# nucleo_breakout.net
KiCad netlist of a schematic drawn in Altium Designer
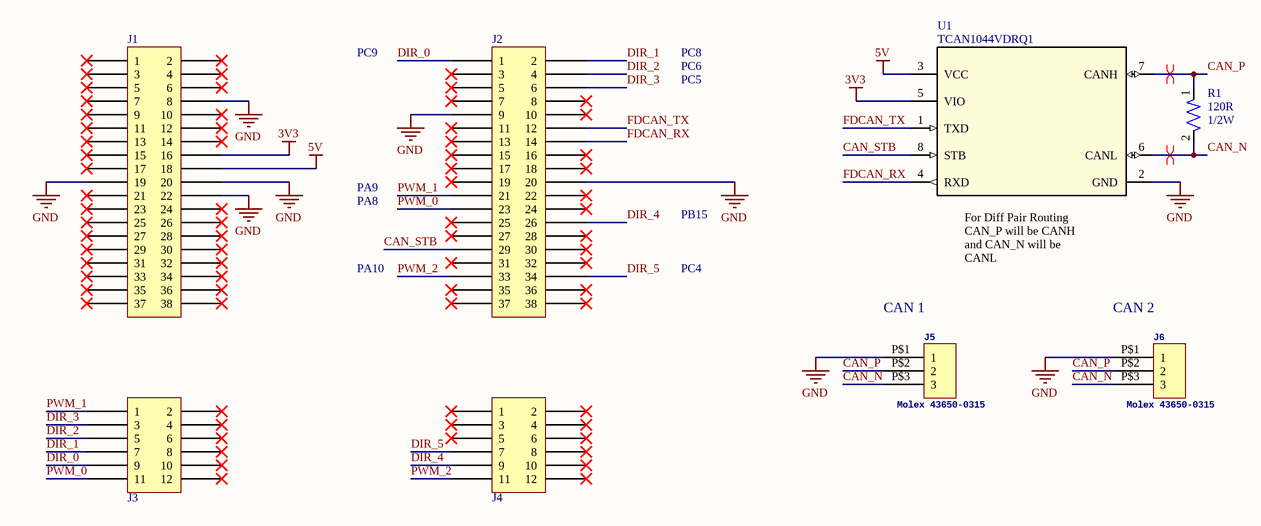
[diagram p0: nucleo_breakout.SchDoc]

(export (version "E")
  (design (tool "Eeschema 10.0.6"))
  (components
    (comp (ref "J1")
      (value "PPPC192LFBN-RC")
      (footprint "CONN-38POS_01")
      (libsource (lib "temp_lib") (part "CONN-38POS-01"))
    )
    (comp (ref "J2")
      (value "PPPC192LFBN-RC")
      (footprint "CONN-38POS_01")
      (libsource (lib "temp_lib") (part "CONN-38POS-01"))
    )
    (comp (ref "J3")
      (value "PPTC062LFBN-RC")
      (footprint "CONN-6POS_01")
      (description "12 Position Header Connector 0.100\" (2.54mm) Through Hole Tin")
      (libsource (lib "temp_lib") (part "CONN-12POS-01"))
    )
    (comp (ref "J4")
      (value "PPTC062LFBN-RC")
      (footprint "CONN-6POS_01")
      (description "12 Position Header Connector 0.100\" (2.54mm) Through Hole Tin")
      (libsource (lib "temp_lib") (part "CONN-12POS-01"))
    )
    (comp (ref "J5")
      (value "Molex 43650-0315")
      (footprint "43650-0315")
      (libsource (lib "Molex Microfit") (part "Micro-Fit Molex 3 Pin Vertical"))
    )
    (comp (ref "J6")
      (value "Molex 43650-0315")
      (footprint "43650-0315")
      (libsource (lib "Molex Microfit") (part "Micro-Fit Molex 3 Pin Vertical"))
    )
    (comp (ref "R1")
      (value "RC1210FR-07120RL")
      (footprint "RES-1210")
      (description "RES 120 OHM 1% 1/2W 1210")
      (fields
        (field (name "TOLERANCE") "1%")
        (field (name "POWER") "1/2W")
        (field (name "RESISTANCE") "120R")
      )
      (libsource (lib "JLC_25") (part "RES-120-0001"))
    )
    (comp (ref "U1")
      (value "TCAN1044VDRQ1")
      (footprint "IC-8SOIC")
      (description "IC TRANSCEIVER 1/1 8SOIC")
      (libsource (lib "JLC_25") (part "IC-CAN-0001"))
    )
  )
  (nets
    (net (code "1") (name "/CAN_N") (class "Default")
      (node (ref "J5") (pin "P$3") (pinfunction "3_P$3") (pintype "passive"))
      (node (ref "J6") (pin "P$3") (pinfunction "3_P$3") (pintype "passive"))
      (node (ref "R1") (pin "2") (pinfunction "2_2") (pintype "passive"))
      (node (ref "U1") (pin "6") (pinfunction "CANL_6") (pintype "bidirectional"))
    )
    (net (code "2") (name "/CAN_P") (class "Default")
      (node (ref "J5") (pin "P$2") (pinfunction "2_P$2") (pintype "passive"))
      (node (ref "J6") (pin "P$2") (pinfunction "2_P$2") (pintype "passive"))
      (node (ref "R1") (pin "1") (pinfunction "1_1") (pintype "passive"))
      (node (ref "U1") (pin "7") (pinfunction "CANH_7") (pintype "bidirectional"))
    )
    (net (code "3") (name "/CAN_STB") (class "Default")
      (node (ref "J2") (pin "29") (pinfunction "29_29") (pintype "passive"))
      (node (ref "U1") (pin "8") (pinfunction "STB_8") (pintype "input"))
    )
    (net (code "4") (name "/DIR_0") (class "Default")
      (node (ref "J2") (pin "1") (pinfunction "1_1") (pintype "passive"))
      (node (ref "J3") (pin "9") (pinfunction "9_9") (pintype "passive"))
    )
    (net (code "5") (name "/DIR_1") (class "Default")
      (node (ref "J2") (pin "2") (pinfunction "2_2") (pintype "passive"))
      (node (ref "J3") (pin "7") (pinfunction "7_7") (pintype "passive"))
    )
    (net (code "6") (name "/DIR_2") (class "Default")
      (node (ref "J2") (pin "4") (pinfunction "4_4") (pintype "passive"))
      (node (ref "J3") (pin "5") (pinfunction "5_5") (pintype "passive"))
    )
    (net (code "7") (name "/DIR_3") (class "Default")
      (node (ref "J2") (pin "6") (pinfunction "6_6") (pintype "passive"))
      (node (ref "J3") (pin "3") (pinfunction "3_3") (pintype "passive"))
    )
    (net (code "8") (name "/DIR_4") (class "Default")
      (node (ref "J2") (pin "26") (pinfunction "26_26") (pintype "passive"))
      (node (ref "J4") (pin "9") (pinfunction "9_9") (pintype "passive"))
    )
    (net (code "9") (name "/DIR_5") (class "Default")
      (node (ref "J2") (pin "34") (pinfunction "34_34") (pintype "passive"))
      (node (ref "J4") (pin "7") (pinfunction "7_7") (pintype "passive"))
    )
    (net (code "10") (name "/FDCAN_RX") (class "Default")
      (node (ref "J2") (pin "14") (pinfunction "14_14") (pintype "passive"))
      (node (ref "U1") (pin "4") (pinfunction "RXD_4") (pintype "output"))
    )
    (net (code "11") (name "/FDCAN_TX") (class "Default")
      (node (ref "J2") (pin "12") (pinfunction "12_12") (pintype "passive"))
      (node (ref "U1") (pin "1") (pinfunction "TXD_1") (pintype "input"))
    )
    (net (code "12") (name "/PWM_0") (class "Default")
      (node (ref "J2") (pin "23") (pinfunction "23_23") (pintype "passive"))
      (node (ref "J3") (pin "11") (pinfunction "11_11") (pintype "passive"))
    )
    (net (code "13") (name "/PWM_1") (class "Default")
      (node (ref "J2") (pin "21") (pinfunction "21_21") (pintype "passive"))
      (node (ref "J3") (pin "1") (pinfunction "1_1") (pintype "passive"))
    )
    (net (code "14") (name "/PWM_2") (class "Default")
      (node (ref "J2") (pin "33") (pinfunction "33_33") (pintype "passive"))
      (node (ref "J4") (pin "11") (pinfunction "11_11") (pintype "passive"))
    )
    (net (code "15") (name "3V3") (class "Default")
      (node (ref "J1") (pin "16") (pinfunction "16_16") (pintype "passive"))
      (node (ref "U1") (pin "5") (pinfunction "VIO_5") (pintype "power_in"))
    )
    (net (code "16") (name "5V") (class "Default")
      (node (ref "J1") (pin "18") (pinfunction "18_18") (pintype "passive"))
      (node (ref "U1") (pin "3") (pinfunction "VCC_3") (pintype "power_in"))
    )
    (net (code "17") (name "GND") (class "Default")
      (node (ref "J1") (pin "19") (pinfunction "19_19") (pintype "passive"))
      (node (ref "J1") (pin "20") (pinfunction "20_20") (pintype "passive"))
      (node (ref "J1") (pin "22") (pinfunction "22_22") (pintype "passive"))
      (node (ref "J1") (pin "8") (pinfunction "8_8") (pintype "passive"))
      (node (ref "J2") (pin "20") (pinfunction "20_20") (pintype "passive"))
      (node (ref "J2") (pin "9") (pinfunction "9_9") (pintype "passive"))
      (node (ref "J5") (pin "P$1") (pinfunction "1_P$1") (pintype "passive"))
      (node (ref "J6") (pin "P$1") (pinfunction "1_P$1") (pintype "passive"))
      (node (ref "U1") (pin "2") (pinfunction "GND_2") (pintype "power_in"))
    )
    (net (code "18") (name "unconnected-(J1-Pad1)") (class "Default")
      (node (ref "J1") (pin "1") (pinfunction "1_1") (pintype "passive+no_connect"))
    )
    (net (code "19") (name "unconnected-(J1-Pad2)") (class "Default")
      (node (ref "J1") (pin "2") (pinfunction "2_2") (pintype "passive+no_connect"))
    )
    (net (code "20") (name "unconnected-(J1-Pad3)") (class "Default")
      (node (ref "J1") (pin "3") (pinfunction "3_3") (pintype "passive+no_connect"))
    )
    (net (code "21") (name "unconnected-(J1-Pad4)") (class "Default")
      (node (ref "J1") (pin "4") (pinfunction "4_4") (pintype "passive+no_connect"))
    )
    (net (code "22") (name "unconnected-(J1-Pad5)") (class "Default")
      (node (ref "J1") (pin "5") (pinfunction "5_5") (pintype "passive+no_connect"))
    )
    (net (code "23") (name "unconnected-(J1-Pad6)") (class "Default")
      (node (ref "J1") (pin "6") (pinfunction "6_6") (pintype "passive+no_connect"))
    )
    (net (code "24") (name "unconnected-(J1-Pad7)") (class "Default")
      (node (ref "J1") (pin "7") (pinfunction "7_7") (pintype "passive+no_connect"))
    )
    (net (code "25") (name "unconnected-(J1-Pad9)") (class "Default")
      (node (ref "J1") (pin "9") (pinfunction "9_9") (pintype "passive+no_connect"))
    )
    (net (code "26") (name "unconnected-(J1-Pad10)") (class "Default")
      (node (ref "J1") (pin "10") (pinfunction "10_10") (pintype "passive+no_connect"))
    )
    (net (code "27") (name "unconnected-(J1-Pad11)") (class "Default")
      (node (ref "J1") (pin "11") (pinfunction "11_11") (pintype "passive+no_connect"))
    )
    (net (code "28") (name "unconnected-(J1-Pad12)") (class "Default")
      (node (ref "J1") (pin "12") (pinfunction "12_12") (pintype "passive+no_connect"))
    )
    (net (code "29") (name "unconnected-(J1-Pad13)") (class "Default")
      (node (ref "J1") (pin "13") (pinfunction "13_13") (pintype "passive+no_connect"))
    )
    (net (code "30") (name "unconnected-(J1-Pad14)") (class "Default")
      (node (ref "J1") (pin "14") (pinfunction "14_14") (pintype "passive+no_connect"))
    )
    (net (code "31") (name "unconnected-(J1-Pad15)") (class "Default")
      (node (ref "J1") (pin "15") (pinfunction "15_15") (pintype "passive+no_connect"))
    )
    (net (code "32") (name "unconnected-(J1-Pad17)") (class "Default")
      (node (ref "J1") (pin "17") (pinfunction "17_17") (pintype "passive+no_connect"))
    )
    (net (code "33") (name "unconnected-(J1-Pad21)") (class "Default")
      (node (ref "J1") (pin "21") (pinfunction "21_21") (pintype "passive+no_connect"))
    )
    (net (code "34") (name "unconnected-(J1-Pad23)") (class "Default")
      (node (ref "J1") (pin "23") (pinfunction "23_23") (pintype "passive+no_connect"))
    )
    (net (code "35") (name "unconnected-(J1-Pad24)") (class "Default")
      (node (ref "J1") (pin "24") (pinfunction "24_24") (pintype "passive+no_connect"))
    )
    (net (code "36") (name "unconnected-(J1-Pad25)") (class "Default")
      (node (ref "J1") (pin "25") (pinfunction "25_25") (pintype "passive+no_connect"))
    )
    (net (code "37") (name "unconnected-(J1-Pad26)") (class "Default")
      (node (ref "J1") (pin "26") (pinfunction "26_26") (pintype "passive+no_connect"))
    )
    (net (code "38") (name "unconnected-(J1-Pad27)") (class "Default")
      (node (ref "J1") (pin "27") (pinfunction "27_27") (pintype "passive+no_connect"))
    )
    (net (code "39") (name "unconnected-(J1-Pad28)") (class "Default")
      (node (ref "J1") (pin "28") (pinfunction "28_28") (pintype "passive+no_connect"))
    )
    (net (code "40") (name "unconnected-(J1-Pad29)") (class "Default")
      (node (ref "J1") (pin "29") (pinfunction "29_29") (pintype "passive+no_connect"))
    )
    (net (code "41") (name "unconnected-(J1-Pad30)") (class "Default")
      (node (ref "J1") (pin "30") (pinfunction "30_30") (pintype "passive+no_connect"))
    )
    (net (code "42") (name "unconnected-(J1-Pad31)") (class "Default")
      (node (ref "J1") (pin "31") (pinfunction "31_31") (pintype "passive+no_connect"))
    )
    (net (code "43") (name "unconnected-(J1-Pad32)") (class "Default")
      (node (ref "J1") (pin "32") (pinfunction "32_32") (pintype "passive+no_connect"))
    )
    (net (code "44") (name "unconnected-(J1-Pad33)") (class "Default")
      (node (ref "J1") (pin "33") (pinfunction "33_33") (pintype "passive+no_connect"))
    )
    (net (code "45") (name "unconnected-(J1-Pad34)") (class "Default")
      (node (ref "J1") (pin "34") (pinfunction "34_34") (pintype "passive+no_connect"))
    )
    (net (code "46") (name "unconnected-(J1-Pad35)") (class "Default")
      (node (ref "J1") (pin "35") (pinfunction "35_35") (pintype "passive+no_connect"))
    )
    (net (code "47") (name "unconnected-(J1-Pad36)") (class "Default")
      (node (ref "J1") (pin "36") (pinfunction "36_36") (pintype "passive+no_connect"))
    )
    (net (code "48") (name "unconnected-(J1-Pad37)") (class "Default")
      (node (ref "J1") (pin "37") (pinfunction "37_37") (pintype "passive+no_connect"))
    )
    (net (code "49") (name "unconnected-(J1-Pad38)") (class "Default")
      (node (ref "J1") (pin "38") (pinfunction "38_38") (pintype "passive+no_connect"))
    )
    (net (code "50") (name "unconnected-(J2-Pad3)") (class "Default")
      (node (ref "J2") (pin "3") (pinfunction "3_3") (pintype "passive+no_connect"))
    )
    (net (code "51") (name "unconnected-(J2-Pad5)") (class "Default")
      (node (ref "J2") (pin "5") (pinfunction "5_5") (pintype "passive+no_connect"))
    )
    (net (code "52") (name "unconnected-(J2-Pad7)") (class "Default")
      (node (ref "J2") (pin "7") (pinfunction "7_7") (pintype "passive+no_connect"))
    )
    (net (code "53") (name "unconnected-(J2-Pad8)") (class "Default")
      (node (ref "J2") (pin "8") (pinfunction "8_8") (pintype "passive+no_connect"))
    )
    (net (code "54") (name "unconnected-(J2-Pad10)") (class "Default")
      (node (ref "J2") (pin "10") (pinfunction "10_10") (pintype "passive+no_connect"))
    )
    (net (code "55") (name "unconnected-(J2-Pad11)") (class "Default")
      (node (ref "J2") (pin "11") (pinfunction "11_11") (pintype "passive+no_connect"))
    )
    (net (code "56") (name "unconnected-(J2-Pad13)") (class "Default")
      (node (ref "J2") (pin "13") (pinfunction "13_13") (pintype "passive+no_connect"))
    )
    (net (code "57") (name "unconnected-(J2-Pad15)") (class "Default")
      (node (ref "J2") (pin "15") (pinfunction "15_15") (pintype "passive+no_connect"))
    )
    (net (code "58") (name "unconnected-(J2-Pad16)") (class "Default")
      (node (ref "J2") (pin "16") (pinfunction "16_16") (pintype "passive+no_connect"))
    )
    (net (code "59") (name "unconnected-(J2-Pad17)") (class "Default")
      (node (ref "J2") (pin "17") (pinfunction "17_17") (pintype "passive+no_connect"))
    )
    (net (code "60") (name "unconnected-(J2-Pad18)") (class "Default")
      (node (ref "J2") (pin "18") (pinfunction "18_18") (pintype "passive+no_connect"))
    )
    (net (code "61") (name "unconnected-(J2-Pad19)") (class "Default")
      (node (ref "J2") (pin "19") (pinfunction "19_19") (pintype "passive+no_connect"))
    )
    (net (code "62") (name "unconnected-(J2-Pad22)") (class "Default")
      (node (ref "J2") (pin "22") (pinfunction "22_22") (pintype "passive+no_connect"))
    )
    (net (code "63") (name "unconnected-(J2-Pad24)") (class "Default")
      (node (ref "J2") (pin "24") (pinfunction "24_24") (pintype "passive+no_connect"))
    )
    (net (code "64") (name "unconnected-(J2-Pad25)") (class "Default")
      (node (ref "J2") (pin "25") (pinfunction "25_25") (pintype "passive+no_connect"))
    )
    (net (code "65") (name "unconnected-(J2-Pad27)") (class "Default")
      (node (ref "J2") (pin "27") (pinfunction "27_27") (pintype "passive+no_connect"))
    )
    (net (code "66") (name "unconnected-(J2-Pad28)") (class "Default")
      (node (ref "J2") (pin "28") (pinfunction "28_28") (pintype "passive+no_connect"))
    )
    (net (code "67") (name "unconnected-(J2-Pad30)") (class "Default")
      (node (ref "J2") (pin "30") (pinfunction "30_30") (pintype "passive+no_connect"))
    )
    (net (code "68") (name "unconnected-(J2-Pad31)") (class "Default")
      (node (ref "J2") (pin "31") (pinfunction "31_31") (pintype "passive+no_connect"))
    )
    (net (code "69") (name "unconnected-(J2-Pad32)") (class "Default")
      (node (ref "J2") (pin "32") (pinfunction "32_32") (pintype "passive+no_connect"))
    )
    (net (code "70") (name "unconnected-(J2-Pad35)") (class "Default")
      (node (ref "J2") (pin "35") (pinfunction "35_35") (pintype "passive+no_connect"))
    )
    (net (code "71") (name "unconnected-(J2-Pad36)") (class "Default")
      (node (ref "J2") (pin "36") (pinfunction "36_36") (pintype "passive+no_connect"))
    )
    (net (code "72") (name "unconnected-(J2-Pad37)") (class "Default")
      (node (ref "J2") (pin "37") (pinfunction "37_37") (pintype "passive+no_connect"))
    )
    (net (code "73") (name "unconnected-(J2-Pad38)") (class "Default")
      (node (ref "J2") (pin "38") (pinfunction "38_38") (pintype "passive+no_connect"))
    )
    (net (code "74") (name "unconnected-(J3-Pad2)") (class "Default")
      (node (ref "J3") (pin "2") (pinfunction "2_2") (pintype "passive+no_connect"))
    )
    (net (code "75") (name "unconnected-(J3-Pad4)") (class "Default")
      (node (ref "J3") (pin "4") (pinfunction "4_4") (pintype "passive+no_connect"))
    )
    (net (code "76") (name "unconnected-(J3-Pad6)") (class "Default")
      (node (ref "J3") (pin "6") (pinfunction "6_6") (pintype "passive+no_connect"))
    )
    (net (code "77") (name "unconnected-(J3-Pad8)") (class "Default")
      (node (ref "J3") (pin "8") (pinfunction "8_8") (pintype "passive+no_connect"))
    )
    (net (code "78") (name "unconnected-(J3-Pad10)") (class "Default")
      (node (ref "J3") (pin "10") (pinfunction "10_10") (pintype "passive+no_connect"))
    )
    (net (code "79") (name "unconnected-(J3-Pad12)") (class "Default")
      (node (ref "J3") (pin "12") (pinfunction "12_12") (pintype "passive+no_connect"))
    )
    (net (code "80") (name "unconnected-(J4-Pad1)") (class "Default")
      (node (ref "J4") (pin "1") (pinfunction "1_1") (pintype "passive+no_connect"))
    )
    (net (code "81") (name "unconnected-(J4-Pad2)") (class "Default")
      (node (ref "J4") (pin "2") (pinfunction "2_2") (pintype "passive+no_connect"))
    )
    (net (code "82") (name "unconnected-(J4-Pad3)") (class "Default")
      (node (ref "J4") (pin "3") (pinfunction "3_3") (pintype "passive+no_connect"))
    )
    (net (code "83") (name "unconnected-(J4-Pad4)") (class "Default")
      (node (ref "J4") (pin "4") (pinfunction "4_4") (pintype "passive+no_connect"))
    )
    (net (code "84") (name "unconnected-(J4-Pad5)") (class "Default")
      (node (ref "J4") (pin "5") (pinfunction "5_5") (pintype "passive+no_connect"))
    )
    (net (code "85") (name "unconnected-(J4-Pad6)") (class "Default")
      (node (ref "J4") (pin "6") (pinfunction "6_6") (pintype "passive+no_connect"))
    )
    (net (code "86") (name "unconnected-(J4-Pad8)") (class "Default")
      (node (ref "J4") (pin "8") (pinfunction "8_8") (pintype "passive+no_connect"))
    )
    (net (code "87") (name "unconnected-(J4-Pad10)") (class "Default")
      (node (ref "J4") (pin "10") (pinfunction "10_10") (pintype "passive+no_connect"))
    )
    (net (code "88") (name "unconnected-(J4-Pad12)") (class "Default")
      (node (ref "J4") (pin "12") (pinfunction "12_12") (pintype "passive+no_connect"))
    )
  )
)
